# MINIBLDC.net
KiCad netlist of a schematic drawn in Altium Designer
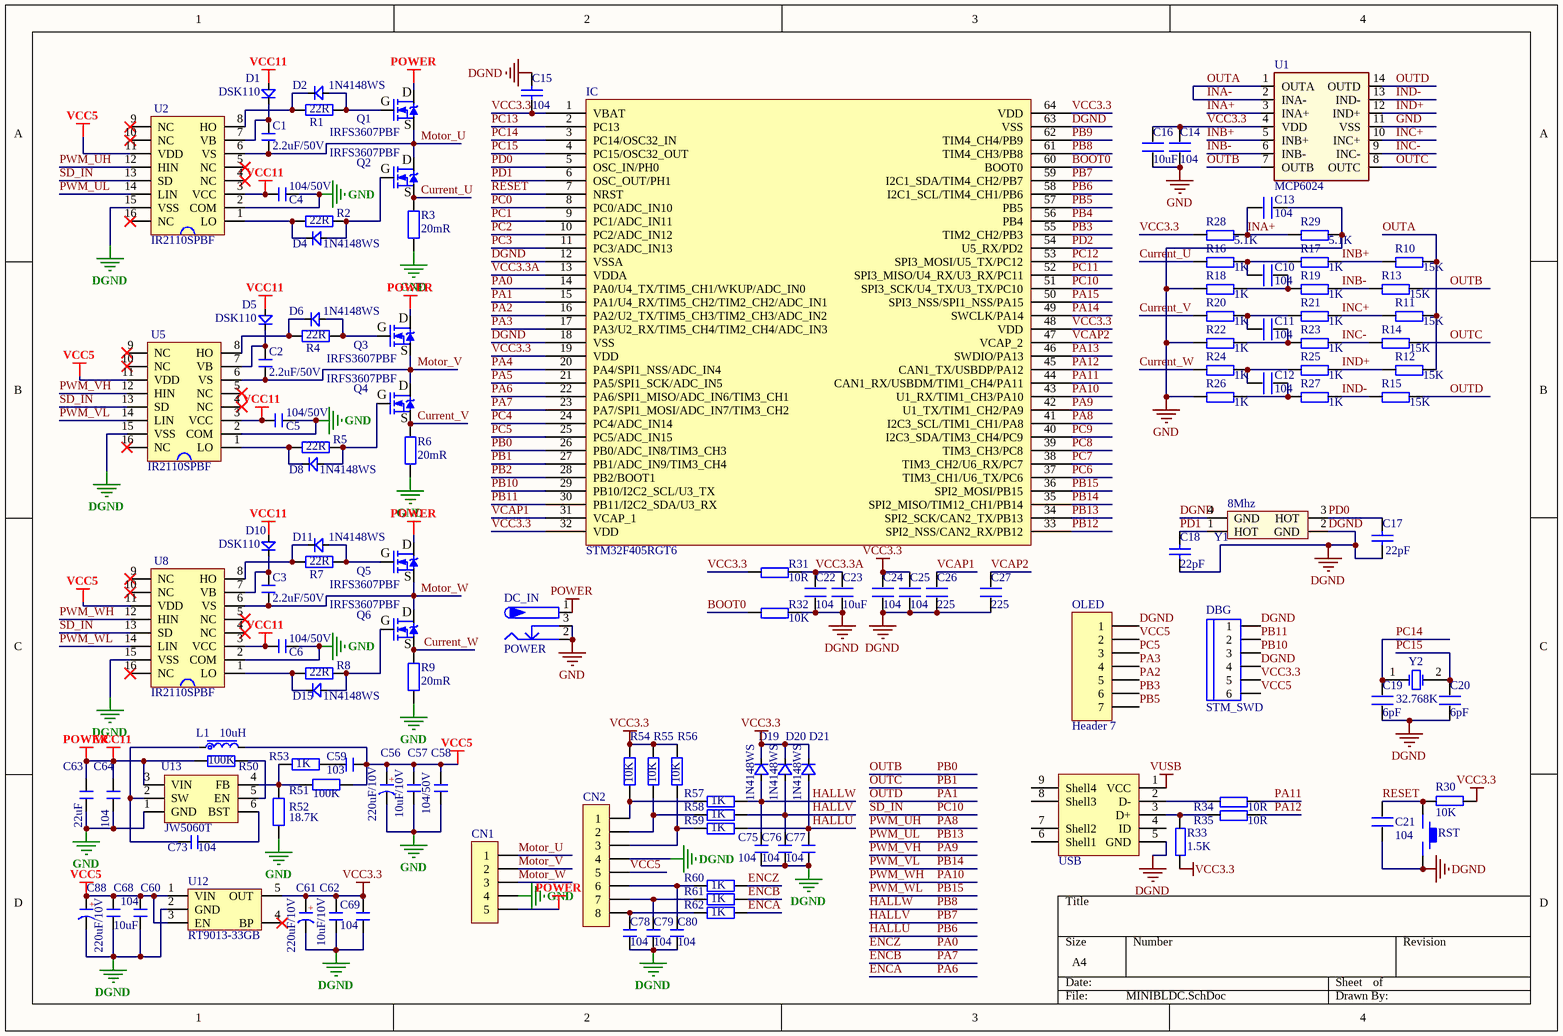
[diagram p0: MINIBLDC.SchDoc]

(export (version "E")
  (design (tool "Eeschema 10.0.6"))
  (components
    (comp (ref "C1")
      (value "2.2uF/50V")
      (footprint "C 0603")
      (description "无极性贴片电容")
      (fields (field (name "版权归属") "源创客"))
      (libsource (lib "电阻-电容-电感") (part "C"))
    )
    (comp (ref "C2")
      (value "2.2uF/50V")
      (footprint "C 0603")
      (description "无极性贴片电容")
      (fields (field (name "版权归属") "源创客"))
      (libsource (lib "电阻-电容-电感") (part "C"))
    )
    (comp (ref "C3")
      (value "2.2uF/50V")
      (footprint "C 0603")
      (description "无极性贴片电容")
      (fields (field (name "版权归属") "源创客"))
      (libsource (lib "电阻-电容-电感") (part "C"))
    )
    (comp (ref "C4")
      (value "104/50V")
      (footprint "C 0603")
      (description "无极性贴片电容")
      (fields (field (name "版权归属") "源创客"))
      (libsource (lib "电阻-电容-电感") (part "C"))
    )
    (comp (ref "C5")
      (value "104/50V")
      (footprint "C 0603")
      (description "无极性贴片电容")
      (fields (field (name "版权归属") "源创客"))
      (libsource (lib "电阻-电容-电感") (part "C"))
    )
    (comp (ref "C6")
      (value "104/50V")
      (footprint "C 0603")
      (description "无极性贴片电容")
      (fields (field (name "版权归属") "源创客"))
      (libsource (lib "电阻-电容-电感") (part "C"))
    )
    (comp (ref "C10") (value "104") (footprint "C 0603") (libsource (lib "IMX6UL_ALPHA(底板)_V2.0") (part "C")))
    (comp (ref "C11") (value "104") (footprint "C 0603") (libsource (lib "IMX6UL_ALPHA(底板)_V2.0") (part "C")))
    (comp (ref "C12") (value "104") (footprint "C 0603") (libsource (lib "IMX6UL_ALPHA(底板)_V2.0") (part "C")))
    (comp (ref "C13") (value "104") (footprint "C 0603") (libsource (lib "IMX6UL_ALPHA(底板)_V2.0") (part "C")))
    (comp (ref "C14") (value "104") (footprint "C 0603") (libsource (lib "IMX6UL_ALPHA(底板)_V2.0") (part "C")))
    (comp (ref "C15") (value "104") (footprint "C 0603") (libsource (lib "L476") (part "CAP")))
    (comp (ref "C16")
      (value "10uF")
      (footprint "C 0603")
      (libsource (lib "IMX6UL_ALPHA(底板)_V2.0") (part "C"))
    )
    (comp (ref "C17") (value "22pF") (footprint "C 0603") (libsource (lib "L476") (part "CAP")))
    (comp (ref "C18") (value "22pF") (footprint "C 0603") (libsource (lib "L476") (part "CAP")))
    (comp (ref "C19")
      (value "6pF")
      (footprint "C 0603")
      (libsource (lib "WarShip V3 STM32103封装库") (part "C"))
    )
    (comp (ref "C20")
      (value "6pF")
      (footprint "C 0603")
      (libsource (lib "WarShip V3 STM32103封装库") (part "C"))
    )
    (comp (ref "C21")
      (value "104")
      (footprint "C 0603")
      (libsource (lib "WarShip V3 STM32103封装库") (part "C"))
    )
    (comp (ref "C22")
      (value "104")
      (footprint "C 0603")
      (libsource (lib "WarShip V3 STM32103封装库") (part "C"))
    )
    (comp (ref "C23")
      (value "10uF")
      (footprint "C 0603")
      (libsource (lib "WarShip V3 STM32103封装库") (part "C"))
    )
    (comp (ref "C24")
      (value "104")
      (footprint "C 0603")
      (libsource (lib "WarShip V3 STM32103封装库") (part "C"))
    )
    (comp (ref "C25")
      (value "104")
      (footprint "C 0603")
      (libsource (lib "WarShip V3 STM32103封装库") (part "C"))
    )
    (comp (ref "C26")
      (value "225")
      (footprint "C 0603")
      (libsource (lib "WarShip V3 STM32103封装库") (part "C"))
    )
    (comp (ref "C27")
      (value "225")
      (footprint "C 0603")
      (libsource (lib "WarShip V3 STM32103封装库") (part "C"))
    )
    (comp (ref "C56")
      (value "220uF/10V")
      (footprint "CM D(6.3*5.4)")
      (description "贴片电解电容")
      (fields (field (name "版权归属") "源创客"))
      (libsource (lib "电阻-电容-电感") (part "C-CM"))
    )
    (comp (ref "C57")
      (value "10uF/10V")
      (footprint "C 0603")
      (description "无极性贴片电容")
      (fields (field (name "版权归属") "源创客"))
      (libsource (lib "电阻-电容-电感") (part "C"))
    )
    (comp (ref "C58")
      (value "104/50V")
      (footprint "C 0603")
      (description "无极性贴片电容")
      (fields (field (name "版权归属") "源创客"))
      (libsource (lib "电阻-电容-电感") (part "C"))
    )
    (comp (ref "C59")
      (value "103")
      (footprint "C 0603")
      (description "无极性贴片电容")
      (fields (field (name "版权归属") "源创客"))
      (libsource (lib "电阻-电容-电感") (part "C"))
    )
    (comp (ref "C60")
      (value "104")
      (footprint "C 0603")
      (description "无极性贴片电容")
      (fields (field (name "版权归属") "源创客"))
      (libsource (lib "电阻-电容-电感") (part "C"))
    )
    (comp (ref "C61")
      (value "220uF/10V")
      (footprint "CM D(6.3*5.4)")
      (description "贴片电解电容")
      (fields (field (name "版权归属") "源创客"))
      (libsource (lib "电阻-电容-电感") (part "C-CM"))
    )
    (comp (ref "C62")
      (value "10uF/10V")
      (footprint "C 0603")
      (description "无极性贴片电容")
      (fields (field (name "版权归属") "源创客"))
      (libsource (lib "电阻-电容-电感") (part "C"))
    )
    (comp (ref "C63")
      (value "22uF")
      (footprint "C 0805")
      (description "无极性贴片电容")
      (fields (field (name "版权归属") "源创客"))
      (libsource (lib "电阻-电容-电感") (part "C"))
    )
    (comp (ref "C64")
      (value "104")
      (footprint "C 0603")
      (description "无极性贴片电容")
      (fields (field (name "版权归属") "源创客"))
      (libsource (lib "电阻-电容-电感") (part "C"))
    )
    (comp (ref "C68")
      (value "10uF")
      (footprint "C 0603")
      (description "无极性贴片电容")
      (fields (field (name "版权归属") "源创客"))
      (libsource (lib "电阻-电容-电感") (part "C"))
    )
    (comp (ref "C69")
      (value "104")
      (footprint "C 0603")
      (description "无极性贴片电容")
      (fields (field (name "版权归属") "源创客"))
      (libsource (lib "电阻-电容-电感") (part "C"))
    )
    (comp (ref "C73")
      (value "104")
      (footprint "C 0603")
      (description "无极性贴片电容")
      (fields (field (name "版权归属") "源创客"))
      (libsource (lib "电阻-电容-电感") (part "C"))
    )
    (comp (ref "C75")
      (value "104")
      (footprint "C 0603")
      (description "无极性贴片电容")
      (fields (field (name "版权归属") "源创客"))
      (libsource (lib "电阻-电容-电感") (part "C"))
    )
    (comp (ref "C76")
      (value "104")
      (footprint "C 0603")
      (description "无极性贴片电容")
      (fields (field (name "版权归属") "源创客"))
      (libsource (lib "电阻-电容-电感") (part "C"))
    )
    (comp (ref "C77")
      (value "104")
      (footprint "C 0603")
      (description "无极性贴片电容")
      (fields (field (name "版权归属") "源创客"))
      (libsource (lib "电阻-电容-电感") (part "C"))
    )
    (comp (ref "C78")
      (value "104")
      (footprint "C 0603")
      (description "无极性贴片电容")
      (fields (field (name "版权归属") "源创客"))
      (libsource (lib "电阻-电容-电感") (part "C"))
    )
    (comp (ref "C79")
      (value "104")
      (footprint "C 0603")
      (description "无极性贴片电容")
      (fields (field (name "版权归属") "源创客"))
      (libsource (lib "电阻-电容-电感") (part "C"))
    )
    (comp (ref "C80")
      (value "104")
      (footprint "C 0603")
      (description "无极性贴片电容")
      (fields (field (name "版权归属") "源创客"))
      (libsource (lib "电阻-电容-电感") (part "C"))
    )
    (comp (ref "C88")
      (value "220uF/10V")
      (footprint "CM D(6.3*5.4)")
      (description "贴片电解电容")
      (fields (field (name "版权归属") "源创客"))
      (libsource (lib "电阻-电容-电感") (part "C-CM"))
    )
    (comp (ref "CN1")
      (value "HDR-1X5")
      (footprint "KF7620-5P")
      (description "5P接插件")
      (fields (field (name "版权归属") "源创客"))
      (libsource (lib "接插件") (part "Header 5"))
    )
    (comp (ref "CN2")
      (value "HDR-1X8")
      (footprint "HDR2.54-LI-8P")
      (description "8P接插件")
      (fields (field (name "版权归属") "源创客"))
      (libsource (lib "接插件") (part "Header 8"))
    )
    (comp (ref "D1")
      (value "DSK110")
      (footprint "SOD-123F")
      (description "通用二极管 100V-1A")
      (fields (field (name "版权归属") "源创客"))
      (libsource (lib "二极管-整流桥") (part "DSK110"))
    )
    (comp (ref "D2")
      (value "1N4148WS")
      (footprint "SOD-323")
      (description "通用二极管 700V-1A")
      (fields (field (name "版权归属") "源创客"))
      (libsource (lib "二极管-整流桥") (part "FR107"))
    )
    (comp (ref "D4")
      (value "1N4148WS")
      (footprint "SOD-323")
      (description "通用二极管 700V-1A")
      (fields (field (name "版权归属") "源创客"))
      (libsource (lib "二极管-整流桥") (part "FR107"))
    )
    (comp (ref "D5")
      (value "DSK110")
      (footprint "SOD-123F")
      (description "通用二极管 100V-1A")
      (fields (field (name "版权归属") "源创客"))
      (libsource (lib "二极管-整流桥") (part "DSK110"))
    )
    (comp (ref "D6")
      (value "1N4148WS")
      (footprint "SOD-323")
      (description "通用二极管 700V-1A")
      (fields (field (name "版权归属") "源创客"))
      (libsource (lib "二极管-整流桥") (part "FR107"))
    )
    (comp (ref "D8")
      (value "1N4148WS")
      (footprint "SOD-323")
      (description "通用二极管 700V-1A")
      (fields (field (name "版权归属") "源创客"))
      (libsource (lib "二极管-整流桥") (part "FR107"))
    )
    (comp (ref "D10")
      (value "DSK110")
      (footprint "SOD-123F")
      (description "通用二极管 100V-1A")
      (fields (field (name "版权归属") "源创客"))
      (libsource (lib "二极管-整流桥") (part "DSK110"))
    )
    (comp (ref "D11")
      (value "1N4148WS")
      (footprint "SOD-323")
      (description "通用二极管 700V-1A")
      (fields (field (name "版权归属") "源创客"))
      (libsource (lib "二极管-整流桥") (part "FR107"))
    )
    (comp (ref "D15")
      (value "1N4148WS")
      (footprint "SOD-323")
      (description "通用二极管 700V-1A")
      (fields (field (name "版权归属") "源创客"))
      (libsource (lib "二极管-整流桥") (part "FR107"))
    )
    (comp (ref "D19")
      (value "1N4148WS")
      (footprint "SOD-323")
      (description "通用二极管 1000V-1A")
      (fields (field (name "版权归属") "源创客"))
      (libsource (lib "二极管-整流桥") (part "RS1M"))
    )
    (comp (ref "D20")
      (value "1N4148WS")
      (footprint "SOD-323")
      (description "通用二极管 1000V-1A")
      (fields (field (name "版权归属") "源创客"))
      (libsource (lib "二极管-整流桥") (part "RS1M"))
    )
    (comp (ref "D21")
      (value "1N4148WS")
      (footprint "SOD-323")
      (description "通用二极管 1000V-1A")
      (fields (field (name "版权归属") "源创客"))
      (libsource (lib "二极管-整流桥") (part "RS1M"))
    )
    (comp (ref "DBG") (value "STM_SWD") (footprint "SH1.0-6P") (libsource (lib "MiniFly ") (part "HEAD6")))
    (comp (ref "DC_IN")
      (value "POWER")
      (footprint "DC10B")
      (description "低压电源接口")
      (fields (field (name "版权归属") "源创客"))
      (libsource (lib "IMX6UL_ALPHA(底板)_V2.0") (part "P-DC"))
    )
    (comp (ref "IC")
      (value "STM32F405RGT6")
      (footprint "LQFP64 10X10_L")
      (description "Flaah:256/RAM:48/IO:51")
      (libsource (lib "ATKF405 V1.1") (part "STM32F405RGT6"))
    )
    (comp (ref "L1")
      (value "10uH")
      (footprint "L-SMD-0420")
      (description "功率屏蔽电感")
      (fields (field (name "版权归属") "源创客"))
      (libsource (lib "电阻-电容-电感") (part "L-CDRH"))
    )
    (comp (ref "OLED")
      (value "Header 7")
      (footprint "HDR2.54-M-LI-7P")
      (description "Header, 7-Pin")
      (fields (field (name "PUBLISHER") "Altium Limited"))
      (libsource (lib "Miscellaneous Connectors") (part "Header 7"))
    )
    (comp (ref "Q1")
      (value "IRFS3607PBF")
      (footprint "TO263-3B")
      (description "NMOS 75V+80A 7.4mΩ")
      (fields (field (name "版权归属") "源创客"))
      (libsource (lib "场效应管-可控硅") (part "IRFS3607PBF"))
    )
    (comp (ref "Q2")
      (value "IRFS3607PBF")
      (footprint "TO263-3B")
      (description "NMOS 75V+80A 7.4mΩ")
      (fields (field (name "版权归属") "源创客"))
      (libsource (lib "场效应管-可控硅") (part "IRFS3607PBF"))
    )
    (comp (ref "Q3")
      (value "IRFS3607PBF")
      (footprint "TO263-3B")
      (description "NMOS 75V+80A 7.4mΩ")
      (fields (field (name "版权归属") "源创客"))
      (libsource (lib "场效应管-可控硅") (part "IRFS3607PBF"))
    )
    (comp (ref "Q4")
      (value "IRFS3607PBF")
      (footprint "TO263-3B")
      (description "NMOS 75V+80A 7.4mΩ")
      (fields (field (name "版权归属") "源创客"))
      (libsource (lib "场效应管-可控硅") (part "IRFS3607PBF"))
    )
    (comp (ref "Q5")
      (value "IRFS3607PBF")
      (footprint "TO263-3B")
      (description "NMOS 75V+80A 7.4mΩ")
      (fields (field (name "版权归属") "源创客"))
      (libsource (lib "场效应管-可控硅") (part "IRFS3607PBF"))
    )
    (comp (ref "Q6")
      (value "IRFS3607PBF")
      (footprint "TO263-3B")
      (description "NMOS 75V+80A 7.4mΩ")
      (fields (field (name "版权归属") "源创客"))
      (libsource (lib "场效应管-可控硅") (part "IRFS3607PBF"))
    )
    (comp (ref "R1")
      (value "22R")
      (footprint "R 0603")
      (description "贴片电阻")
      (fields (field (name "版权归属") "源创客"))
      (libsource (lib "电阻-电容-电感") (part "R"))
    )
    (comp (ref "R2")
      (value "22R")
      (footprint "R 0603")
      (description "贴片电阻")
      (fields (field (name "版权归属") "源创客"))
      (libsource (lib "电阻-电容-电感") (part "R"))
    )
    (comp (ref "R3")
      (value "20mR")
      (footprint "R 2512_L")
      (description "贴片电阻")
      (fields (field (name "版权归属") "源创客"))
      (libsource (lib "电阻-电容-电感") (part "R"))
    )
    (comp (ref "R4")
      (value "22R")
      (footprint "R 0603")
      (description "贴片电阻")
      (fields (field (name "版权归属") "源创客"))
      (libsource (lib "电阻-电容-电感") (part "R"))
    )
    (comp (ref "R5")
      (value "22R")
      (footprint "R 0603")
      (description "贴片电阻")
      (fields (field (name "版权归属") "源创客"))
      (libsource (lib "电阻-电容-电感") (part "R"))
    )
    (comp (ref "R6")
      (value "20mR")
      (footprint "R 2512_L")
      (description "贴片电阻")
      (fields (field (name "版权归属") "源创客"))
      (libsource (lib "电阻-电容-电感") (part "R"))
    )
    (comp (ref "R7")
      (value "22R")
      (footprint "R 0603")
      (description "贴片电阻")
      (fields (field (name "版权归属") "源创客"))
      (libsource (lib "电阻-电容-电感") (part "R"))
    )
    (comp (ref "R8")
      (value "22R")
      (footprint "R 0603")
      (description "贴片电阻")
      (fields (field (name "版权归属") "源创客"))
      (libsource (lib "电阻-电容-电感") (part "R"))
    )
    (comp (ref "R9")
      (value "20mR")
      (footprint "R 2512_L")
      (description "贴片电阻")
      (fields (field (name "版权归属") "源创客"))
      (libsource (lib "电阻-电容-电感") (part "R"))
    )
    (comp (ref "R10") (value "15K") (footprint "R 0603") (libsource (lib "IMX6UL_ALPHA(底板)_V2.0") (part "R")))
    (comp (ref "R11") (value "15K") (footprint "R 0603") (libsource (lib "IMX6UL_ALPHA(底板)_V2.0") (part "R")))
    (comp (ref "R12") (value "15K") (footprint "R 0603") (libsource (lib "IMX6UL_ALPHA(底板)_V2.0") (part "R")))
    (comp (ref "R13") (value "15K") (footprint "R 0603") (libsource (lib "IMX6UL_ALPHA(底板)_V2.0") (part "R")))
    (comp (ref "R14") (value "15K") (footprint "R 0603") (libsource (lib "IMX6UL_ALPHA(底板)_V2.0") (part "R")))
    (comp (ref "R15") (value "15K") (footprint "R 0603") (libsource (lib "IMX6UL_ALPHA(底板)_V2.0") (part "R")))
    (comp (ref "R16") (value "1K") (footprint "R 0603") (libsource (lib "IMX6UL_ALPHA(底板)_V2.0") (part "R")))
    (comp (ref "R17") (value "1K") (footprint "R 0603") (libsource (lib "IMX6UL_ALPHA(底板)_V2.0") (part "R")))
    (comp (ref "R18") (value "1K") (footprint "R 0603") (libsource (lib "IMX6UL_ALPHA(底板)_V2.0") (part "R")))
    (comp (ref "R19") (value "1K") (footprint "R 0603") (libsource (lib "IMX6UL_ALPHA(底板)_V2.0") (part "R")))
    (comp (ref "R20") (value "1K") (footprint "R 0603") (libsource (lib "IMX6UL_ALPHA(底板)_V2.0") (part "R")))
    (comp (ref "R21") (value "1K") (footprint "R 0603") (libsource (lib "IMX6UL_ALPHA(底板)_V2.0") (part "R")))
    (comp (ref "R22") (value "1K") (footprint "R 0603") (libsource (lib "IMX6UL_ALPHA(底板)_V2.0") (part "R")))
    (comp (ref "R23") (value "1K") (footprint "R 0603") (libsource (lib "IMX6UL_ALPHA(底板)_V2.0") (part "R")))
    (comp (ref "R24") (value "1K") (footprint "R 0603") (libsource (lib "IMX6UL_ALPHA(底板)_V2.0") (part "R")))
    (comp (ref "R25") (value "1K") (footprint "R 0603") (libsource (lib "IMX6UL_ALPHA(底板)_V2.0") (part "R")))
    (comp (ref "R26") (value "1K") (footprint "R 0603") (libsource (lib "IMX6UL_ALPHA(底板)_V2.0") (part "R")))
    (comp (ref "R27") (value "1K") (footprint "R 0603") (libsource (lib "IMX6UL_ALPHA(底板)_V2.0") (part "R")))
    (comp (ref "R28")
      (value "5.1K")
      (footprint "R 0603")
      (libsource (lib "IMX6UL_ALPHA(底板)_V2.0") (part "R"))
    )
    (comp (ref "R29")
      (value "5.1K")
      (footprint "R 0603")
      (libsource (lib "IMX6UL_ALPHA(底板)_V2.0") (part "R"))
    )
    (comp (ref "R30")
      (value "10K")
      (footprint "R 0603")
      (libsource (lib "WarShip V3 STM32103封装库") (part "R"))
    )
    (comp (ref "R31")
      (value "10R")
      (footprint "R 0603")
      (libsource (lib "WarShip V3 STM32103封装库") (part "R"))
    )
    (comp (ref "R32")
      (value "10K")
      (footprint "R 0603")
      (libsource (lib "WarShip V3 STM32103封装库") (part "R"))
    )
    (comp (ref "R33")
      (value "1.5K")
      (footprint "R 0603")
      (libsource (lib "WarShip V3 STM32103封装库") (part "R"))
    )
    (comp (ref "R34")
      (value "10R")
      (footprint "R 0603")
      (libsource (lib "WarShip V3 STM32103封装库") (part "R"))
    )
    (comp (ref "R35")
      (value "10R")
      (footprint "R 0603")
      (libsource (lib "WarShip V3 STM32103封装库") (part "R"))
    )
    (comp (ref "R50")
      (value "100K")
      (footprint "R 0603")
      (description "贴片电阻")
      (fields (field (name "版权归属") "源创客"))
      (libsource (lib "电阻-电容-电感") (part "R"))
    )
    (comp (ref "R51")
      (value "100K")
      (footprint "R 0603")
      (description "贴片电阻")
      (fields (field (name "版权归属") "源创客"))
      (libsource (lib "电阻-电容-电感") (part "R"))
    )
    (comp (ref "R52")
      (value "18.7K")
      (footprint "R 0603")
      (description "贴片电阻")
      (fields (field (name "版权归属") "源创客"))
      (libsource (lib "电阻-电容-电感") (part "R"))
    )
    (comp (ref "R53")
      (value "1K")
      (footprint "R 0603")
      (description "贴片电阻")
      (fields (field (name "版权归属") "源创客"))
      (libsource (lib "电阻-电容-电感") (part "R"))
    )
    (comp (ref "R54")
      (value "10K")
      (footprint "R 0603")
      (description "贴片电阻")
      (fields (field (name "版权归属") "源创客"))
      (libsource (lib "电阻-电容-电感") (part "R"))
    )
    (comp (ref "R55")
      (value "10K")
      (footprint "R 0603")
      (description "贴片电阻")
      (fields (field (name "版权归属") "源创客"))
      (libsource (lib "电阻-电容-电感") (part "R"))
    )
    (comp (ref "R56")
      (value "10K")
      (footprint "R 0603")
      (description "贴片电阻")
      (fields (field (name "版权归属") "源创客"))
      (libsource (lib "电阻-电容-电感") (part "R"))
    )
    (comp (ref "R57")
      (value "1K")
      (footprint "R 0603")
      (description "贴片电阻")
      (fields (field (name "版权归属") "源创客"))
      (libsource (lib "电阻-电容-电感") (part "R"))
    )
    (comp (ref "R58")
      (value "1K")
      (footprint "R 0603")
      (description "贴片电阻")
      (fields (field (name "版权归属") "源创客"))
      (libsource (lib "电阻-电容-电感") (part "R"))
    )
    (comp (ref "R59")
      (value "1K")
      (footprint "R 0603")
      (description "贴片电阻")
      (fields (field (name "版权归属") "源创客"))
      (libsource (lib "电阻-电容-电感") (part "R"))
    )
    (comp (ref "R60")
      (value "1K")
      (footprint "R 0603")
      (description "贴片电阻")
      (fields (field (name "版权归属") "源创客"))
      (libsource (lib "电阻-电容-电感") (part "R"))
    )
    (comp (ref "R61")
      (value "1K")
      (footprint "R 0603")
      (description "贴片电阻")
      (fields (field (name "版权归属") "源创客"))
      (libsource (lib "电阻-电容-电感") (part "R"))
    )
    (comp (ref "R62")
      (value "1K")
      (footprint "R 0603")
      (description "贴片电阻")
      (fields (field (name "版权归属") "源创客"))
      (libsource (lib "电阻-电容-电感") (part "R"))
    )
    (comp (ref "RST")
      (value "KEY-SMD")
      (footprint "TSW SMD-3*6*2.5")
      (description "KEY,SMD,324225")
      (libsource (lib "Pandora_STM32L4_Board_V2.4") (part "S-KEY-SMD-324225"))
    )
    (comp (ref "U1") (value "MCP6024") (footprint "SOP14_L") (libsource (lib "MINIBLDC") (part "MCP6024")))
    (comp (ref "U2")
      (value "IR2110SPBF")
      (footprint "SOP16W_L")
      (description "半桥驱动 500V,10-20V  Ton/off=120ns&94ns MT=10nS")
      (libsource (lib "IC芯片") (part "IR2110SPBF"))
    )
    (comp (ref "U5")
      (value "IR2110SPBF")
      (footprint "SOP16W_L")
      (description "半桥驱动 500V,10-20V  Ton/off=120ns&94ns MT=10nS")
      (libsource (lib "IC芯片") (part "IR2110SPBF"))
    )
    (comp (ref "U8")
      (value "IR2110SPBF")
      (footprint "SOP16W_L")
      (description "半桥驱动 500V,10-20V  Ton/off=120ns&94ns MT=10nS")
      (libsource (lib "IC芯片") (part "IR2110SPBF"))
    )
    (comp (ref "U12")
      (value "RT9013-33GB")
      (footprint "SOT23-5N")
      (description "LDO")
      (fields (field (name "版权归属") "源创客"))
      (libsource (lib "LDO和DCDC") (part "LDO RT9193"))
    )
    (comp (ref "U13")
      (value "JW5060T")
      (footprint "SOT23-6L")
      (description "DC降压芯片")
      (libsource (lib "LDO和DCDC") (part "DC JW5060T_6"))
    )
    (comp (ref "USB")
      (value "MICRO-USB")
      (footprint "USB-AB-5S")
      (description "Micro USB 5.9有柱脚长1.25加长针")
      (libsource (lib "Pandora_STM32L4_Board_V2.4") (part "J-MICRO-USB-5S"))
    )
    (comp (ref "Y1")
      (value "8Mhz")
      (footprint "XTAL-3225")
      (description "3225贴片无源晶振")
      (libsource (lib "ALIENTEK_COMPONENT") (part "XTAL_3225"))
    )
    (comp (ref "Y2")
      (value "32.768K")
      (footprint "OSC 3215-2P")
      (description "Crystal Oscillator")
      (fields (field (name "PUBLISHER") "Altium Limited"))
      (libsource (lib "WarShip V3 STM32103封装库") (part "XTAL"))
    )
  )
  (nets
    (net (code "1") (name "/BOOT0") (class "Default")
      (node (ref "IC") (pin "60") (pinfunction "BOOT0_60") (pintype "passive"))
      (node (ref "R32") (pin "1") (pintype "passive"))
    )
    (net (code "2") (name "/Current_U") (class "Default")
      (node (ref "Q2") (pin "3") (pinfunction "S_3") (pintype "passive"))
      (node (ref "R16") (pin "1") (pintype "passive"))
      (node (ref "R3") (pin "2") (pinfunction "2_2") (pintype "passive"))
    )
    (net (code "3") (name "/Current_V") (class "Default")
      (node (ref "Q4") (pin "3") (pinfunction "S_3") (pintype "passive"))
      (node (ref "R20") (pin "1") (pintype "passive"))
      (node (ref "R6") (pin "2") (pinfunction "2_2") (pintype "passive"))
    )
    (net (code "4") (name "/Current_W") (class "Default")
      (node (ref "Q6") (pin "3") (pinfunction "S_3") (pintype "passive"))
      (node (ref "R24") (pin "1") (pintype "passive"))
      (node (ref "R9") (pin "2") (pinfunction "2_2") (pintype "passive"))
    )
    (net (code "5") (name "/ENCA") (class "Default")
      (node (ref "IC") (pin "22") (pinfunction "PA6/SPI1_MISO/ADC_IN6/TIM3_CH1_22") (pintype "passive"))
      (node (ref "R62") (pin "2") (pinfunction "2_2") (pintype "passive"))
    )
    (net (code "6") (name "/ENCB") (class "Default")
      (node (ref "IC") (pin "23") (pinfunction "PA7/SPI1_MOSI/ADC_IN7/TIM3_CH2_23") (pintype "passive"))
      (node (ref "R61") (pin "2") (pinfunction "2_2") (pintype "passive"))
    )
    (net (code "7") (name "/ENCZ") (class "Default")
      (node (ref "IC") (pin "14") (pinfunction "PA0/U4_TX/TIM5_CH1/WKUP/ADC_IN0_14") (pintype "passive"))
      (node (ref "R60") (pin "2") (pinfunction "2_2") (pintype "passive"))
    )
    (net (code "8") (name "/HALLU") (class "Default")
      (node (ref "C77") (pin "1") (pinfunction "1_1") (pintype "passive"))
      (node (ref "D21") (pin "1") (pinfunction "A_1") (pintype "passive"))
      (node (ref "IC") (pin "58") (pinfunction "I2C1_SCL/TIM4_CH1/PB6_58") (pintype "passive"))
      (node (ref "R59") (pin "2") (pinfunction "2_2") (pintype "passive"))
    )
    (net (code "9") (name "/HALLV") (class "Default")
      (node (ref "C76") (pin "1") (pinfunction "1_1") (pintype "passive"))
      (node (ref "D20") (pin "1") (pinfunction "A_1") (pintype "passive"))
      (node (ref "IC") (pin "59") (pinfunction "I2C1_SDA/TIM4_CH2/PB7_59") (pintype "passive"))
      (node (ref "R58") (pin "2") (pinfunction "2_2") (pintype "passive"))
    )
    (net (code "10") (name "/HALLW") (class "Default")
      (node (ref "C75") (pin "1") (pinfunction "1_1") (pintype "passive"))
      (node (ref "D19") (pin "1") (pinfunction "A_1") (pintype "passive"))
      (node (ref "IC") (pin "61") (pinfunction "TIM4_CH3/PB8_61") (pintype "passive"))
      (node (ref "R57") (pin "2") (pinfunction "2_2") (pintype "passive"))
    )
    (net (code "11") (name "/INA+") (class "Default")
      (node (ref "C13") (pin "1") (pintype "passive"))
      (node (ref "R28") (pin "2") (pintype "passive"))
      (node (ref "R29") (pin "1") (pintype "passive"))
      (node (ref "U1") (pin "3") (pinfunction "INA+_3") (pintype "passive"))
    )
    (net (code "12") (name "/INA-") (class "Default")
      (node (ref "R10") (pin "2") (pintype "passive"))
      (node (ref "R11") (pin "2") (pintype "passive"))
      (node (ref "R12") (pin "2") (pintype "passive"))
      (node (ref "U1") (pin "1") (pinfunction "OUTA_1") (pintype "passive"))
      (node (ref "U1") (pin "2") (pinfunction "INA-_2") (pintype "passive"))
    )
    (net (code "13") (name "/INB+") (class "Default")
      (node (ref "R10") (pin "1") (pintype "passive"))
      (node (ref "R17") (pin "2") (pintype "passive"))
      (node (ref "U1") (pin "5") (pinfunction "INB+_5") (pintype "passive"))
    )
    (net (code "14") (name "/INB-") (class "Default")
      (node (ref "R13") (pin "1") (pintype "passive"))
      (node (ref "R19") (pin "2") (pintype "passive"))
      (node (ref "U1") (pin "6") (pinfunction "INB-_6") (pintype "passive"))
    )
    (net (code "15") (name "/INC+") (class "Default")
      (node (ref "R11") (pin "1") (pintype "passive"))
      (node (ref "R21") (pin "2") (pintype "passive"))
      (node (ref "U1") (pin "10") (pinfunction "INC+_10") (pintype "passive"))
    )
    (net (code "16") (name "/INC-") (class "Default")
      (node (ref "R14") (pin "1") (pintype "passive"))
      (node (ref "R23") (pin "2") (pintype "passive"))
      (node (ref "U1") (pin "9") (pinfunction "INC-_9") (pintype "passive"))
    )
    (net (code "17") (name "/IND+") (class "Default")
      (node (ref "R12") (pin "1") (pintype "passive"))
      (node (ref "R25") (pin "2") (pintype "passive"))
      (node (ref "U1") (pin "12") (pinfunction "IND+_12") (pintype "passive"))
    )
    (net (code "18") (name "/IND-") (class "Default")
      (node (ref "R15") (pin "1") (pintype "passive"))
      (node (ref "R27") (pin "2") (pintype "passive"))
      (node (ref "U1") (pin "13") (pinfunction "IND-_13") (pintype "passive"))
    )
    (net (code "19") (name "/Motor_U") (class "Default")
      (node (ref "C1") (pin "1") (pinfunction "1_1") (pintype "passive"))
      (node (ref "CN1") (pin "1") (pinfunction "1_1") (pintype "passive"))
      (node (ref "Q1") (pin "3") (pinfunction "S_3") (pintype "passive"))
      (node (ref "Q2") (pin "2") (pinfunction "D_2") (pintype "passive"))
      (node (ref "U2") (pin "6") (pinfunction "VS_6") (pintype "passive"))
    )
    (net (code "20") (name "/Motor_V") (class "Default")
      (node (ref "C2") (pin "1") (pinfunction "1_1") (pintype "passive"))
      (node (ref "CN1") (pin "2") (pinfunction "2_2") (pintype "passive"))
      (node (ref "Q3") (pin "3") (pinfunction "S_3") (pintype "passive"))
      (node (ref "Q4") (pin "2") (pinfunction "D_2") (pintype "passive"))
      (node (ref "U5") (pin "6") (pinfunction "VS_6") (pintype "passive"))
    )
    (net (code "21") (name "/Motor_W") (class "Default")
      (node (ref "C3") (pin "1") (pinfunction "1_1") (pintype "passive"))
      (node (ref "CN1") (pin "3") (pinfunction "3_3") (pintype "passive"))
      (node (ref "Q5") (pin "3") (pinfunction "S_3") (pintype "passive"))
      (node (ref "Q6") (pin "2") (pinfunction "D_2") (pintype "passive"))
      (node (ref "U8") (pin "6") (pinfunction "VS_6") (pintype "passive"))
    )
    (net (code "22") (name "/OUTB") (class "Default")
      (node (ref "IC") (pin "26") (pinfunction "PB0/ADC_IN8/TIM3_CH3_26") (pintype "passive"))
      (node (ref "R13") (pin "2") (pintype "passive"))
      (node (ref "U1") (pin "7") (pinfunction "OUTB_7") (pintype "passive"))
    )
    (net (code "23") (name "/OUTC") (class "Default")
      (node (ref "IC") (pin "27") (pinfunction "PB1/ADC_IN9/TIM3_CH4_27") (pintype "passive"))
      (node (ref "R14") (pin "2") (pintype "passive"))
      (node (ref "U1") (pin "8") (pinfunction "OUTC_8") (pintype "passive"))
    )
    (net (code "24") (name "/OUTD") (class "Default")
      (node (ref "IC") (pin "15") (pinfunction "PA1/U4_RX/TIM5_CH2/TIM2_CH2/ADC_IN1_15") (pintype "passive"))
      (node (ref "R15") (pin "2") (pintype "passive"))
      (node (ref "U1") (pin "14") (pinfunction "OUTD_14") (pintype "passive"))
    )
    (net (code "25") (name "/PA2") (class "Default")
      (node (ref "IC") (pin "16") (pinfunction "PA2/U2_TX/TIM5_CH3/TIM2_CH3/ADC_IN2_16") (pintype "passive"))
      (node (ref "OLED") (pin "5") (pinfunction "5_5") (pintype "passive"))
    )
    (net (code "26") (name "/PA3") (class "Default")
      (node (ref "IC") (pin "17") (pinfunction "PA3/U2_RX/TIM5_CH4/TIM2_CH4/ADC_IN3_17") (pintype "passive"))
      (node (ref "OLED") (pin "4") (pinfunction "4_4") (pintype "passive"))
    )
    (net (code "27") (name "/PA4") (class "Default")
      (node (ref "IC") (pin "20") (pinfunction "PA4/SPI1_NSS/ADC_IN4_20") (pintype "passive"))
    )
    (net (code "28") (name "/PA5") (class "Default")
      (node (ref "IC") (pin "21") (pinfunction "PA5/SPI1_SCK/ADC_IN5_21") (pintype "passive"))
    )
    (net (code "29") (name "/PA8") (class "Default")
      (node (ref "IC") (pin "41") (pinfunction "I2C3_SCL/TIM1_CH1/PA8_41") (pintype "passive"))
      (node (ref "U2") (pin "12") (pinfunction "HIN_12") (pintype "passive"))
    )
    (net (code "30") (name "/PA9") (class "Default")
      (node (ref "IC") (pin "42") (pinfunction "U1_TX/TIM1_CH2/PA9_42") (pintype "passive"))
      (node (ref "U5") (pin "12") (pinfunction "HIN_12") (pintype "passive"))
    )
    (net (code "31") (name "/PA10") (class "Default")
      (node (ref "IC") (pin "43") (pinfunction "U1_RX/TIM1_CH3/PA10_43") (pintype "passive"))
      (node (ref "U8") (pin "12") (pinfunction "HIN_12") (pintype "passive"))
    )
    (net (code "32") (name "/PA11") (class "Default")
      (node (ref "IC") (pin "44") (pinfunction "CAN1_RX/USBDM/TIM1_CH4/PA11_44") (pintype "passive"))
      (node (ref "R34") (pin "2") (pintype "passive"))
    )
    (net (code "33") (name "/PA12") (class "Default")
      (node (ref "IC") (pin "45") (pinfunction "CAN1_TX/USBDP/PA12_45") (pintype "passive"))
      (node (ref "R35") (pin "2") (pintype "passive"))
    )
    (net (code "34") (name "/PA13") (class "Default")
      (node (ref "IC") (pin "46") (pinfunction "SWDIO/PA13_46") (pintype "passive"))
    )
    (net (code "35") (name "/PA14") (class "Default")
      (node (ref "IC") (pin "49") (pinfunction "SWCLK/PA14_49") (pintype "passive"))
    )
    (net (code "36") (name "/PA15") (class "Default")
      (node (ref "IC") (pin "50") (pinfunction "SPI3_NSS/SPI1_NSS/PA15_50") (pintype "passive"))
    )
    (net (code "37") (name "/PB2") (class "Default")
      (node (ref "IC") (pin "28") (pinfunction "PB2/BOOT1_28") (pintype "passive"))
    )
    (net (code "38") (name "/PB3") (class "Default")
      (node (ref "IC") (pin "55") (pinfunction "TIM2_CH2/PB3_55") (pintype "passive"))
      (node (ref "OLED") (pin "6") (pinfunction "6_6") (pintype "passive"))
    )
    (net (code "39") (name "/PB4") (class "Default")
      (node (ref "IC") (pin "56") (pinfunction "PB4_56") (pintype "passive"))
    )
    (net (code "40") (name "/PB5") (class "Default")
      (node (ref "IC") (pin "57") (pinfunction "PB5_57") (pintype "passive"))
      (node (ref "OLED") (pin "7") (pinfunction "7_7") (pintype "passive"))
    )
    (net (code "41") (name "/PB9") (class "Default")
      (node (ref "IC") (pin "62") (pinfunction "TIM4_CH4/PB9_62") (pintype "passive"))
    )
    (net (code "42") (name "/PB10") (class "Default")
      (node (ref "DBG") (pin "3") (pinfunction "3_3") (pintype "passive"))
      (node (ref "IC") (pin "29") (pinfunction "PB10/I2C2_SCL/U3_TX_29") (pintype "passive"))
    )
    (net (code "43") (name "/PB11") (class "Default")
      (node (ref "DBG") (pin "2") (pinfunction "2_2") (pintype "passive"))
      (node (ref "IC") (pin "30") (pinfunction "PB11/I2C2_SDA/U3_RX_30") (pintype "passive"))
    )
    (net (code "44") (name "/PB12") (class "Default")
      (node (ref "IC") (pin "33") (pinfunction "SPI2_NSS/CAN2_RX/PB12_33") (pintype "passive"))
    )
    (net (code "45") (name "/PB13") (class "Default")
      (node (ref "IC") (pin "34") (pinfunction "SPI2_SCK/CAN2_TX/PB13_34") (pintype "passive"))
      (node (ref "U2") (pin "14") (pinfunction "LIN_14") (pintype "passive"))
    )
    (net (code "46") (name "/PB14") (class "Default")
      (node (ref "IC") (pin "35") (pinfunction "SPI2_MISO/TIM12_CH1/PB14_35") (pintype "passive"))
      (node (ref "U5") (pin "14") (pinfunction "LIN_14") (pintype "passive"))
    )
    (net (code "47") (name "/PB15") (class "Default")
      (node (ref "IC") (pin "36") (pinfunction "SPI2_MOSI/PB15_36") (pintype "passive"))
      (node (ref "U8") (pin "14") (pinfunction "LIN_14") (pintype "passive"))
    )
    (net (code "48") (name "/PC0") (class "Default")
      (node (ref "IC") (pin "8") (pinfunction "PC0/ADC_IN10_8") (pintype "passive"))
    )
    (net (code "49") (name "/PC1") (class "Default")
      (node (ref "IC") (pin "9") (pinfunction "PC1/ADC_IN11_9") (pintype "passive"))
    )
    (net (code "50") (name "/PC2") (class "Default")
      (node (ref "IC") (pin "10") (pinfunction "PC2/ADC_IN12_10") (pintype "passive"))
    )
    (net (code "51") (name "/PC3") (class "Default")
      (node (ref "IC") (pin "11") (pinfunction "PC3/ADC_IN13_11") (pintype "passive"))
    )
    (net (code "52") (name "/PC4") (class "Default")
      (node (ref "IC") (pin "24") (pinfunction "PC4/ADC_IN14_24") (pintype "passive"))
    )
    (net (code "53") (name "/PC5") (class "Default")
      (node (ref "IC") (pin "25") (pinfunction "PC5/ADC_IN15_25") (pintype "passive"))
      (node (ref "OLED") (pin "3") (pinfunction "3_3") (pintype "passive"))
    )
    (net (code "54") (name "/PC6") (class "Default")
      (node (ref "IC") (pin "37") (pinfunction "TIM3_CH1/U6_TX/PC6_37") (pintype "passive"))
    )
    (net (code "55") (name "/PC7") (class "Default")
      (node (ref "IC") (pin "38") (pinfunction "TIM3_CH2/U6_RX/PC7_38") (pintype "passive"))
    )
    (net (code "56") (name "/PC8") (class "Default")
      (node (ref "IC") (pin "39") (pinfunction "TIM3_CH3/PC8_39") (pintype "passive"))
    )
    (net (code "57") (name "/PC9") (class "Default")
      (node (ref "IC") (pin "40") (pinfunction "I2C3_SDA/TIM3_CH4/PC9_40") (pintype "passive"))
    )
    (net (code "58") (name "/PC10") (class "Default")
      (node (ref "IC") (pin "51") (pinfunction "SPI3_SCK/U4_TX/U3_TX/PC10_51") (pintype "passive"))
      (node (ref "U2") (pin "13") (pinfunction "SD_13") (pintype "passive"))
      (node (ref "U5") (pin "13") (pinfunction "SD_13") (pintype "passive"))
      (node (ref "U8") (pin "13") (pinfunction "SD_13") (pintype "passive"))
    )
    (net (code "59") (name "/PC11") (class "Default")
      (node (ref "IC") (pin "52") (pinfunction "SPI3_MISO/U4_RX/U3_RX/PC11_52") (pintype "passive"))
    )
    (net (code "60") (name "/PC12") (class "Default")
      (node (ref "IC") (pin "53") (pinfunction "SPI3_MOSI/U5_TX/PC12_53") (pintype "passive"))
    )
    (net (code "61") (name "/PC13") (class "Default")
      (node (ref "IC") (pin "2") (pinfunction "PC13_2") (pintype "passive"))
    )
    (net (code "62") (name "/PC14") (class "Default")
      (node (ref "C19") (pin "2") (pintype "passive"))
      (node (ref "IC") (pin "3") (pinfunction "PC14/OSC32_IN_3") (pintype "passive"))
      (node (ref "Y2") (pin "1") (pinfunction "OSC1_1") (pintype "passive"))
    )
    (net (code "63") (name "/PC15") (class "Default")
      (node (ref "C20") (pin "2") (pintype "passive"))
      (node (ref "IC") (pin "4") (pinfunction "PC15/OSC32_OUT_4") (pintype "passive"))
      (node (ref "Y2") (pin "2") (pinfunction "OSC2_2") (pintype "passive"))
    )
    (net (code "64") (name "/PD0") (class "Default")
      (node (ref "C17") (pin "2") (pinfunction "2_2") (pintype "passive"))
      (node (ref "IC") (pin "5") (pinfunction "OSC_IN/PH0_5") (pintype "passive"))
      (node (ref "Y1") (pin "3") (pinfunction "HOT_3") (pintype "passive"))
    )
    (net (code "65") (name "/PD1") (class "Default")
      (node (ref "C18") (pin "2") (pinfunction "2_2") (pintype "passive"))
      (node (ref "IC") (pin "6") (pinfunction "OSC_OUT/PH1_6") (pintype "passive"))
      (node (ref "Y1") (pin "1") (pinfunction "HOT_1") (pintype "passive"))
    )
    (net (code "66") (name "/PD2") (class "Default")
      (node (ref "IC") (pin "54") (pinfunction "U5_RX/PD2_54") (pintype "passive"))
    )
    (net (code "67") (name "/RESET") (class "Default")
      (node (ref "C21") (pin "2") (pintype "passive"))
      (node (ref "IC") (pin "7") (pinfunction "NRST_7") (pintype "passive"))
      (node (ref "R30") (pin "2") (pintype "passive"))
      (node (ref "RST") (pin "1") (pinfunction "1_1") (pintype "passive"))
    )
    (net (code "68") (name "/VCAP1") (class "Default")
      (node (ref "C26") (pin "2") (pintype "passive"))
      (node (ref "IC") (pin "31") (pinfunction "VCAP_1_31") (pintype "passive"))
    )
    (net (code "69") (name "/VCAP2") (class "Default")
      (node (ref "C27") (pin "2") (pintype "passive"))
      (node (ref "IC") (pin "47") (pinfunction "VCAP_2_47") (pintype "passive"))
    )
    (net (code "70") (name "/VCC3.3A") (class "Default")
      (node (ref "C22") (pin "2") (pintype "passive"))
      (node (ref "C23") (pin "2") (pintype "passive"))
      (node (ref "IC") (pin "13") (pinfunction "VDDA_13") (pintype "passive"))
      (node (ref "R31") (pin "2") (pintype "passive"))
    )
    (net (code "71") (name "DGND") (class "Default")
      (node (ref "C15") (pin "1") (pinfunction "1_1") (pintype "passive"))
      (node (ref "C17") (pin "1") (pinfunction "1_1") (pintype "passive"))
      (node (ref "C18") (pin "1") (pinfunction "1_1") (pintype "passive"))
      (node (ref "C19") (pin "1") (pintype "passive"))
      (node (ref "C20") (pin "1") (pintype "passive"))
      (node (ref "C21") (pin "1") (pintype "passive"))
      (node (ref "C22") (pin "1") (pintype "passive"))
      (node (ref "C23") (pin "1") (pintype "passive"))
      (node (ref "C24") (pin "1") (pintype "passive"))
      (node (ref "C25") (pin "1") (pintype "passive"))
      (node (ref "C26") (pin "1") (pintype "passive"))
      (node (ref "C27") (pin "1") (pintype "passive"))
      (node (ref "C60") (pin "2") (pinfunction "2_2") (pintype "passive"))
      (node (ref "C61") (pin "2") (pinfunction "K_2") (pintype "passive"))
      (node (ref "C62") (pin "2") (pinfunction "2_2") (pintype "passive"))
      (node (ref "C68") (pin "2") (pinfunction "2_2") (pintype "passive"))
      (node (ref "C69") (pin "2") (pinfunction "2_2") (pintype "passive"))
      (node (ref "C75") (pin "2") (pinfunction "2_2") (pintype "passive"))
      (node (ref "C76") (pin "2") (pinfunction "2_2") (pintype "passive"))
      (node (ref "C77") (pin "2") (pinfunction "2_2") (pintype "passive"))
      (node (ref "C78") (pin "2") (pinfunction "2_2") (pintype "passive"))
      (node (ref "C79") (pin "2") (pinfunction "2_2") (pintype "passive"))
      (node (ref "C80") (pin "2") (pinfunction "2_2") (pintype "passive"))
      (node (ref "C88") (pin "2") (pinfunction "K_2") (pintype "passive"))
      (node (ref "CN2") (pin "4") (pinfunction "4_4") (pintype "passive"))
      (node (ref "DBG") (pin "1") (pinfunction "1_1") (pintype "passive"))
      (node (ref "DBG") (pin "4") (pinfunction "4_4") (pintype "passive"))
      (node (ref "IC") (pin "12") (pinfunction "VSSA_12") (pintype "passive"))
      (node (ref "IC") (pin "18") (pinfunction "VSS_18") (pintype "passive"))
      (node (ref "IC") (pin "63") (pinfunction "VSS_63") (pintype "passive"))
      (node (ref "OLED") (pin "1") (pinfunction "1_1") (pintype "passive"))
      (node (ref "R32") (pin "2") (pintype "passive"))
      (node (ref "RST") (pin "2") (pinfunction "2_2") (pintype "passive"))
      (node (ref "U12") (pin "2") (pinfunction "GND_2") (pintype "passive"))
      (node (ref "U2") (pin "15") (pinfunction "VSS_15") (pintype "passive"))
      (node (ref "U5") (pin "15") (pinfunction "VSS_15") (pintype "passive"))
      (node (ref "U8") (pin "15") (pinfunction "VSS_15") (pintype "passive"))
      (node (ref "USB") (pin "5") (pinfunction "GND_5") (pintype "passive"))
      (node (ref "Y1") (pin "2") (pinfunction "GND_2") (pintype "passive"))
      (node (ref "Y1") (pin "4") (pinfunction "GND_4") (pintype "passive"))
    )
    (net (code "72") (name "GND") (class "Default")
      (node (ref "C13") (pin "2") (pintype "passive"))
      (node (ref "C14") (pin "1") (pintype "passive"))
      (node (ref "C16") (pin "1") (pintype "passive"))
      (node (ref "C4") (pin "1") (pinfunction "1_1") (pintype "passive"))
      (node (ref "C5") (pin "1") (pinfunction "1_1") (pintype "passive"))
      (node (ref "C56") (pin "2") (pinfunction "K_2") (pintype "passive"))
      (node (ref "C57") (pin "2") (pinfunction "2_2") (pintype "passive"))
      (node (ref "C58") (pin "2") (pinfunction "2_2") (pintype "passive"))
      (node (ref "C6") (pin "1") (pinfunction "1_1") (pintype "passive"))
      (node (ref "C63") (pin "2") (pinfunction "2_2") (pintype "passive"))
      (node (ref "C64") (pin "2") (pinfunction "2_2") (pintype "passive"))
      (node (ref "CN1") (pin "4") (pinfunction "4_4") (pintype "passive"))
      (node (ref "DC_IN") (pin "2") (pintype "power_in"))
      (node (ref "DC_IN") (pin "3") (pintype "power_in"))
      (node (ref "R18") (pin "1") (pintype "passive"))
      (node (ref "R22") (pin "1") (pintype "passive"))
      (node (ref "R26") (pin "1") (pintype "passive"))
      (node (ref "R29") (pin "2") (pintype "passive"))
      (node (ref "R3") (pin "1") (pinfunction "1_1") (pintype "passive"))
      (node (ref "R52") (pin "2") (pinfunction "2_2") (pintype "passive"))
      (node (ref "R6") (pin "1") (pinfunction "1_1") (pintype "passive"))
      (node (ref "R9") (pin "1") (pinfunction "1_1") (pintype "passive"))
      (node (ref "U1") (pin "11") (pinfunction "VSS_11") (pintype "passive"))
      (node (ref "U13") (pin "1") (pinfunction "GND_1") (pintype "passive"))
      (node (ref "U2") (pin "2") (pinfunction "COM_2") (pintype "passive"))
      (node (ref "U5") (pin "2") (pinfunction "COM_2") (pintype "passive"))
      (node (ref "U8") (pin "2") (pinfunction "COM_2") (pintype "passive"))
    )
    (net (code "73") (name "Net-(C10-Pad1)") (class "Default")
      (node (ref "C10") (pin "1") (pintype "passive"))
      (node (ref "R16") (pin "2") (pintype "passive"))
      (node (ref "R17") (pin "1") (pintype "passive"))
    )
    (net (code "74") (name "Net-(C10-Pad2)") (class "Default")
      (node (ref "C10") (pin "2") (pintype "passive"))
      (node (ref "R18") (pin "2") (pintype "passive"))
      (node (ref "R19") (pin "1") (pintype "passive"))
    )
    (net (code "75") (name "Net-(C11-Pad1)") (class "Default")
      (node (ref "C11") (pin "1") (pintype "passive"))
      (node (ref "R20") (pin "2") (pintype "passive"))
      (node (ref "R21") (pin "1") (pintype "passive"))
    )
    (net (code "76") (name "Net-(C11-Pad2)") (class "Default")
      (node (ref "C11") (pin "2") (pintype "passive"))
      (node (ref "R22") (pin "2") (pintype "passive"))
      (node (ref "R23") (pin "1") (pintype "passive"))
    )
    (net (code "77") (name "Net-(C12-Pad1)") (class "Default")
      (node (ref "C12") (pin "1") (pintype "passive"))
      (node (ref "R24") (pin "2") (pintype "passive"))
      (node (ref "R25") (pin "1") (pintype "passive"))
    )
    (net (code "78") (name "Net-(C12-Pad2)") (class "Default")
      (node (ref "C12") (pin "2") (pintype "passive"))
      (node (ref "R26") (pin "2") (pintype "passive"))
      (node (ref "R27") (pin "1") (pintype "passive"))
    )
    (net (code "79") (name "Net-(C59-Pad1)") (class "Default")
      (node (ref "C59") (pin "1") (pinfunction "1_1") (pintype "passive"))
      (node (ref "R53") (pin "2") (pinfunction "2_2") (pintype "passive"))
    )
    (net (code "80") (name "Net-(C78-Pad1)") (class "Default")
      (node (ref "C78") (pin "1") (pinfunction "1_1") (pintype "passive"))
      (node (ref "CN2") (pin "8") (pinfunction "8_8") (pintype "passive"))
      (node (ref "R62") (pin "1") (pinfunction "1_1") (pintype "passive"))
    )
    (net (code "81") (name "Net-(C79-Pad1)") (class "Default")
      (node (ref "C79") (pin "1") (pinfunction "1_1") (pintype "passive"))
      (node (ref "CN2") (pin "7") (pinfunction "7_7") (pintype "passive"))
      (node (ref "R61") (pin "1") (pinfunction "1_1") (pintype "passive"))
    )
    (net (code "82") (name "Net-(C80-Pad1)") (class "Default")
      (node (ref "C80") (pin "1") (pinfunction "1_1") (pintype "passive"))
      (node (ref "CN2") (pin "6") (pinfunction "6_6") (pintype "passive"))
      (node (ref "R60") (pin "1") (pinfunction "1_1") (pintype "passive"))
    )
    (net (code "83") (name "Net-(CN2-Pad1)") (class "Default")
      (node (ref "CN2") (pin "1") (pinfunction "1_1") (pintype "passive"))
      (node (ref "R54") (pin "2") (pinfunction "2_2") (pintype "passive"))
      (node (ref "R57") (pin "1") (pinfunction "1_1") (pintype "passive"))
    )
    (net (code "84") (name "Net-(CN2-Pad2)") (class "Default")
      (node (ref "CN2") (pin "2") (pinfunction "2_2") (pintype "passive"))
      (node (ref "R55") (pin "2") (pinfunction "2_2") (pintype "passive"))
      (node (ref "R58") (pin "1") (pinfunction "1_1") (pintype "passive"))
    )
    (net (code "85") (name "Net-(CN2-Pad3)") (class "Default")
      (node (ref "CN2") (pin "3") (pinfunction "3_3") (pintype "passive"))
      (node (ref "R56") (pin "2") (pinfunction "2_2") (pintype "passive"))
      (node (ref "R59") (pin "1") (pinfunction "1_1") (pintype "passive"))
    )
    (net (code "86") (name "Net-(D1-K)") (class "Default")
      (node (ref "C1") (pin "2") (pinfunction "2_2") (pintype "passive"))
      (node (ref "D1") (pin "2") (pinfunction "K_2") (pintype "passive"))
      (node (ref "U2") (pin "7") (pinfunction "VB_7") (pintype "passive"))
    )
    (net (code "87") (name "Net-(D2-A)") (class "Default")
      (node (ref "D2") (pin "1") (pinfunction "A_1") (pintype "passive"))
      (node (ref "Q1") (pin "1") (pinfunction "G_1") (pintype "passive"))
      (node (ref "R1") (pin "2") (pinfunction "2_2") (pintype "passive"))
    )
    (net (code "88") (name "Net-(D2-K)") (class "Default")
      (node (ref "D2") (pin "2") (pinfunction "K_2") (pintype "passive"))
      (node (ref "R1") (pin "1") (pinfunction "1_1") (pintype "passive"))
      (node (ref "U2") (pin "8") (pinfunction "HO_8") (pintype "passive"))
    )
    (net (code "89") (name "Net-(D4-A)") (class "Default")
      (node (ref "D4") (pin "1") (pinfunction "A_1") (pintype "passive"))
      (node (ref "Q2") (pin "1") (pinfunction "G_1") (pintype "passive"))
      (node (ref "R2") (pin "2") (pinfunction "2_2") (pintype "passive"))
    )
    (net (code "90") (name "Net-(D4-K)") (class "Default")
      (node (ref "D4") (pin "2") (pinfunction "K_2") (pintype "passive"))
      (node (ref "R2") (pin "1") (pinfunction "1_1") (pintype "passive"))
      (node (ref "U2") (pin "1") (pinfunction "LO_1") (pintype "passive"))
    )
    (net (code "91") (name "Net-(D5-K)") (class "Default")
      (node (ref "C2") (pin "2") (pinfunction "2_2") (pintype "passive"))
      (node (ref "D5") (pin "2") (pinfunction "K_2") (pintype "passive"))
      (node (ref "U5") (pin "7") (pinfunction "VB_7") (pintype "passive"))
    )
    (net (code "92") (name "Net-(D6-A)") (class "Default")
      (node (ref "D6") (pin "1") (pinfunction "A_1") (pintype "passive"))
      (node (ref "Q3") (pin "1") (pinfunction "G_1") (pintype "passive"))
      (node (ref "R4") (pin "2") (pinfunction "2_2") (pintype "passive"))
    )
    (net (code "93") (name "Net-(D6-K)") (class "Default")
      (node (ref "D6") (pin "2") (pinfunction "K_2") (pintype "passive"))
      (node (ref "R4") (pin "1") (pinfunction "1_1") (pintype "passive"))
      (node (ref "U5") (pin "8") (pinfunction "HO_8") (pintype "passive"))
    )
    (net (code "94") (name "Net-(D8-A)") (class "Default")
      (node (ref "D8") (pin "1") (pinfunction "A_1") (pintype "passive"))
      (node (ref "Q4") (pin "1") (pinfunction "G_1") (pintype "passive"))
      (node (ref "R5") (pin "2") (pinfunction "2_2") (pintype "passive"))
    )
    (net (code "95") (name "Net-(D8-K)") (class "Default")
      (node (ref "D8") (pin "2") (pinfunction "K_2") (pintype "passive"))
      (node (ref "R5") (pin "1") (pinfunction "1_1") (pintype "passive"))
      (node (ref "U5") (pin "1") (pinfunction "LO_1") (pintype "passive"))
    )
    (net (code "96") (name "Net-(D10-K)") (class "Default")
      (node (ref "C3") (pin "2") (pinfunction "2_2") (pintype "passive"))
      (node (ref "D10") (pin "2") (pinfunction "K_2") (pintype "passive"))
      (node (ref "U8") (pin "7") (pinfunction "VB_7") (pintype "passive"))
    )
    (net (code "97") (name "Net-(D11-A)") (class "Default")
      (node (ref "D11") (pin "1") (pinfunction "A_1") (pintype "passive"))
      (node (ref "Q5") (pin "1") (pinfunction "G_1") (pintype "passive"))
      (node (ref "R7") (pin "2") (pinfunction "2_2") (pintype "passive"))
    )
    (net (code "98") (name "Net-(D11-K)") (class "Default")
      (node (ref "D11") (pin "2") (pinfunction "K_2") (pintype "passive"))
      (node (ref "R7") (pin "1") (pinfunction "1_1") (pintype "passive"))
      (node (ref "U8") (pin "8") (pinfunction "HO_8") (pintype "passive"))
    )
    (net (code "99") (name "Net-(D15-A)") (class "Default")
      (node (ref "D15") (pin "1") (pinfunction "A_1") (pintype "passive"))
      (node (ref "Q6") (pin "1") (pinfunction "G_1") (pintype "passive"))
      (node (ref "R8") (pin "2") (pinfunction "2_2") (pintype "passive"))
    )
    (net (code "100") (name "Net-(D15-K)") (class "Default")
      (node (ref "D15") (pin "2") (pinfunction "K_2") (pintype "passive"))
      (node (ref "R8") (pin "1") (pinfunction "1_1") (pintype "passive"))
      (node (ref "U8") (pin "1") (pinfunction "LO_1") (pintype "passive"))
    )
    (net (code "101") (name "Net-(U13-BST)") (class "Default")
      (node (ref "C73") (pin "1") (pinfunction "1_1") (pintype "passive"))
      (node (ref "U13") (pin "6") (pinfunction "BST_6") (pintype "passive"))
    )
    (net (code "102") (name "Net-(U13-EN)") (class "Default")
      (node (ref "R50") (pin "2") (pinfunction "2_2") (pintype "passive"))
      (node (ref "U13") (pin "5") (pinfunction "EN_5") (pintype "passive"))
    )
    (net (code "103") (name "Net-(U13-FB)") (class "Default")
      (node (ref "R51") (pin "1") (pinfunction "1_1") (pintype "passive"))
      (node (ref "R52") (pin "1") (pinfunction "1_1") (pintype "passive"))
      (node (ref "R53") (pin "1") (pinfunction "1_1") (pintype "passive"))
      (node (ref "U13") (pin "4") (pinfunction "FB_4") (pintype "passive"))
    )
    (net (code "104") (name "Net-(U13-SW)") (class "Default")
      (node (ref "C73") (pin "2") (pinfunction "2_2") (pintype "passive"))
      (node (ref "L1") (pin "1") (pinfunction "1_1") (pintype "passive"))
      (node (ref "U13") (pin "2") (pinfunction "SW_2") (pintype "passive"))
    )
    (net (code "105") (name "Net-(USB-D+)") (class "Default")
      (node (ref "R33") (pin "2") (pintype "passive"))
      (node (ref "R35") (pin "1") (pintype "passive"))
      (node (ref "USB") (pin "3") (pinfunction "D+_3") (pintype "passive"))
    )
    (net (code "106") (name "Net-(USB-D-)") (class "Default")
      (node (ref "R34") (pin "1") (pintype "passive"))
      (node (ref "USB") (pin "2") (pinfunction "D-_2") (pintype "passive"))
    )
    (net (code "107") (name "POWER") (class "Default")
      (node (ref "C4") (pin "2") (pinfunction "2_2") (pintype "passive"))
      (node (ref "C5") (pin "2") (pinfunction "2_2") (pintype "passive"))
      (node (ref "C6") (pin "2") (pinfunction "2_2") (pintype "passive"))
      (node (ref "C63") (pin "1") (pinfunction "1_1") (pintype "passive"))
      (node (ref "C64") (pin "1") (pinfunction "1_1") (pintype "passive"))
      (node (ref "CN1") (pin "5") (pinfunction "5_5") (pintype "passive"))
      (node (ref "D1") (pin "1") (pinfunction "A_1") (pintype "passive"))
      (node (ref "D10") (pin "1") (pinfunction "A_1") (pintype "passive"))
      (node (ref "D5") (pin "1") (pinfunction "A_1") (pintype "passive"))
      (node (ref "DC_IN") (pin "1") (pintype "power_in"))
      (node (ref "Q1") (pin "2") (pinfunction "D_2") (pintype "passive"))
      (node (ref "Q3") (pin "2") (pinfunction "D_2") (pintype "passive"))
      (node (ref "Q5") (pin "2") (pinfunction "D_2") (pintype "passive"))
      (node (ref "R50") (pin "1") (pinfunction "1_1") (pintype "passive"))
      (node (ref "U13") (pin "3") (pinfunction "VIN_3") (pintype "passive"))
      (node (ref "U2") (pin "3") (pinfunction "VCC_3") (pintype "passive"))
      (node (ref "U5") (pin "3") (pinfunction "VCC_3") (pintype "passive"))
      (node (ref "U8") (pin "3") (pinfunction "VCC_3") (pintype "passive"))
    )
    (net (code "108") (name "VCC3.3") (class "Default")
      (node (ref "C14") (pin "2") (pintype "passive"))
      (node (ref "C15") (pin "2") (pinfunction "2_2") (pintype "passive"))
      (node (ref "C16") (pin "2") (pintype "passive"))
      (node (ref "C24") (pin "2") (pintype "passive"))
      (node (ref "C25") (pin "2") (pintype "passive"))
      (node (ref "C61") (pin "1") (pinfunction "A_1") (pintype "passive"))
      (node (ref "C62") (pin "1") (pinfunction "1_1") (pintype "passive"))
      (node (ref "C69") (pin "1") (pinfunction "1_1") (pintype "passive"))
      (node (ref "D19") (pin "2") (pinfunction "K_2") (pintype "passive"))
      (node (ref "D20") (pin "2") (pinfunction "K_2") (pintype "passive"))
      (node (ref "D21") (pin "2") (pinfunction "K_2") (pintype "passive"))
      (node (ref "DBG") (pin "5") (pinfunction "5_5") (pintype "passive"))
      (node (ref "IC") (pin "1") (pinfunction "VBAT_1") (pintype "passive"))
      (node (ref "IC") (pin "19") (pinfunction "VDD_19") (pintype "passive"))
      (node (ref "IC") (pin "32") (pinfunction "VDD_32") (pintype "passive"))
      (node (ref "IC") (pin "48") (pinfunction "VDD_48") (pintype "passive"))
      (node (ref "IC") (pin "64") (pinfunction "VDD_64") (pintype "passive"))
      (node (ref "R28") (pin "1") (pintype "passive"))
      (node (ref "R30") (pin "1") (pintype "passive"))
      (node (ref "R31") (pin "1") (pintype "passive"))
      (node (ref "R33") (pin "1") (pintype "passive"))
      (node (ref "R54") (pin "1") (pinfunction "1_1") (pintype "passive"))
      (node (ref "R55") (pin "1") (pinfunction "1_1") (pintype "passive"))
      (node (ref "R56") (pin "1") (pinfunction "1_1") (pintype "passive"))
      (node (ref "U1") (pin "4") (pinfunction "VDD_4") (pintype "passive"))
      (node (ref "U12") (pin "5") (pinfunction "OUT_5") (pintype "passive"))
    )
    (net (code "109") (name "VCC5") (class "Default")
      (node (ref "C56") (pin "1") (pinfunction "A_1") (pintype "passive"))
      (node (ref "C57") (pin "1") (pinfunction "1_1") (pintype "passive"))
      (node (ref "C58") (pin "1") (pinfunction "1_1") (pintype "passive"))
      (node (ref "C59") (pin "2") (pinfunction "2_2") (pintype "passive"))
      (node (ref "C60") (pin "1") (pinfunction "1_1") (pintype "passive"))
      (node (ref "C68") (pin "1") (pinfunction "1_1") (pintype "passive"))
      (node (ref "C88") (pin "1") (pinfunction "A_1") (pintype "passive"))
      (node (ref "CN2") (pin "5") (pinfunction "5_5") (pintype "passive"))
      (node (ref "DBG") (pin "6") (pinfunction "6_6") (pintype "passive"))
      (node (ref "L1") (pin "2") (pinfunction "2_2") (pintype "passive"))
      (node (ref "OLED") (pin "2") (pinfunction "2_2") (pintype "passive"))
      (node (ref "R51") (pin "2") (pinfunction "2_2") (pintype "passive"))
      (node (ref "U12") (pin "1") (pinfunction "VIN_1") (pintype "passive"))
      (node (ref "U12") (pin "3") (pinfunction "EN_3") (pintype "passive"))
      (node (ref "U2") (pin "11") (pinfunction "VDD_11") (pintype "passive"))
      (node (ref "U5") (pin "11") (pinfunction "VDD_11") (pintype "passive"))
      (node (ref "U8") (pin "11") (pinfunction "VDD_11") (pintype "passive"))
    )
    (net (code "110") (name "VUSB") (class "Default")
      (node (ref "USB") (pin "1") (pinfunction "VCC_1") (pintype "passive"))
    )
    (net (code "111") (name "unconnected-(U2-NC-Pad4)") (class "Default")
      (node (ref "U2") (pin "4") (pinfunction "NC_4") (pintype "passive+no_connect"))
    )
    (net (code "112") (name "unconnected-(U2-NC-Pad5)") (class "Default")
      (node (ref "U2") (pin "5") (pinfunction "NC_5") (pintype "passive+no_connect"))
    )
    (net (code "113") (name "unconnected-(U2-NC-Pad9)") (class "Default")
      (node (ref "U2") (pin "9") (pinfunction "NC_9") (pintype "passive+no_connect"))
    )
    (net (code "114") (name "unconnected-(U2-NC-Pad10)") (class "Default")
      (node (ref "U2") (pin "10") (pinfunction "NC_10") (pintype "passive+no_connect"))
    )
    (net (code "115") (name "unconnected-(U2-NC-Pad16)") (class "Default")
      (node (ref "U2") (pin "16") (pinfunction "NC_16") (pintype "passive+no_connect"))
    )
    (net (code "116") (name "unconnected-(U5-NC-Pad4)") (class "Default")
      (node (ref "U5") (pin "4") (pinfunction "NC_4") (pintype "passive+no_connect"))
    )
    (net (code "117") (name "unconnected-(U5-NC-Pad5)") (class "Default")
      (node (ref "U5") (pin "5") (pinfunction "NC_5") (pintype "passive+no_connect"))
    )
    (net (code "118") (name "unconnected-(U5-NC-Pad9)") (class "Default")
      (node (ref "U5") (pin "9") (pinfunction "NC_9") (pintype "passive+no_connect"))
    )
    (net (code "119") (name "unconnected-(U5-NC-Pad10)") (class "Default")
      (node (ref "U5") (pin "10") (pinfunction "NC_10") (pintype "passive+no_connect"))
    )
    (net (code "120") (name "unconnected-(U5-NC-Pad16)") (class "Default")
      (node (ref "U5") (pin "16") (pinfunction "NC_16") (pintype "passive+no_connect"))
    )
    (net (code "121") (name "unconnected-(U8-NC-Pad4)") (class "Default")
      (node (ref "U8") (pin "4") (pinfunction "NC_4") (pintype "passive+no_connect"))
    )
    (net (code "122") (name "unconnected-(U8-NC-Pad5)") (class "Default")
      (node (ref "U8") (pin "5") (pinfunction "NC_5") (pintype "passive+no_connect"))
    )
    (net (code "123") (name "unconnected-(U8-NC-Pad9)") (class "Default")
      (node (ref "U8") (pin "9") (pinfunction "NC_9") (pintype "passive+no_connect"))
    )
    (net (code "124") (name "unconnected-(U8-NC-Pad10)") (class "Default")
      (node (ref "U8") (pin "10") (pinfunction "NC_10") (pintype "passive+no_connect"))
    )
    (net (code "125") (name "unconnected-(U8-NC-Pad16)") (class "Default")
      (node (ref "U8") (pin "16") (pinfunction "NC_16") (pintype "passive+no_connect"))
    )
    (net (code "126") (name "unconnected-(U12-BP-Pad4)") (class "Default")
      (node (ref "U12") (pin "4") (pinfunction "BP_4") (pintype "passive+no_connect"))
    )
    (net (code "127") (name "unconnected-(USB-ID-Pad4)") (class "Default")
      (node (ref "USB") (pin "4") (pinfunction "ID_4") (pintype "passive"))
    )
    (net (code "128") (name "unconnected-(USB-Shell1-Pad6)") (class "Default")
      (node (ref "USB") (pin "6") (pinfunction "Shell1_6") (pintype "passive"))
    )
    (net (code "129") (name "unconnected-(USB-Shell2-Pad7)") (class "Default")
      (node (ref "USB") (pin "7") (pinfunction "Shell2_7") (pintype "passive"))
    )
    (net (code "130") (name "unconnected-(USB-Shell3-Pad8)") (class "Default")
      (node (ref "USB") (pin "8") (pinfunction "Shell3_8") (pintype "passive"))
    )
    (net (code "131") (name "unconnected-(USB-Shell4-Pad9)") (class "Default")
      (node (ref "USB") (pin "9") (pinfunction "Shell4_9") (pintype "passive"))
    )
  )
)
